# Main_old.net
KiCad netlist of a schematic drawn in EAGLE
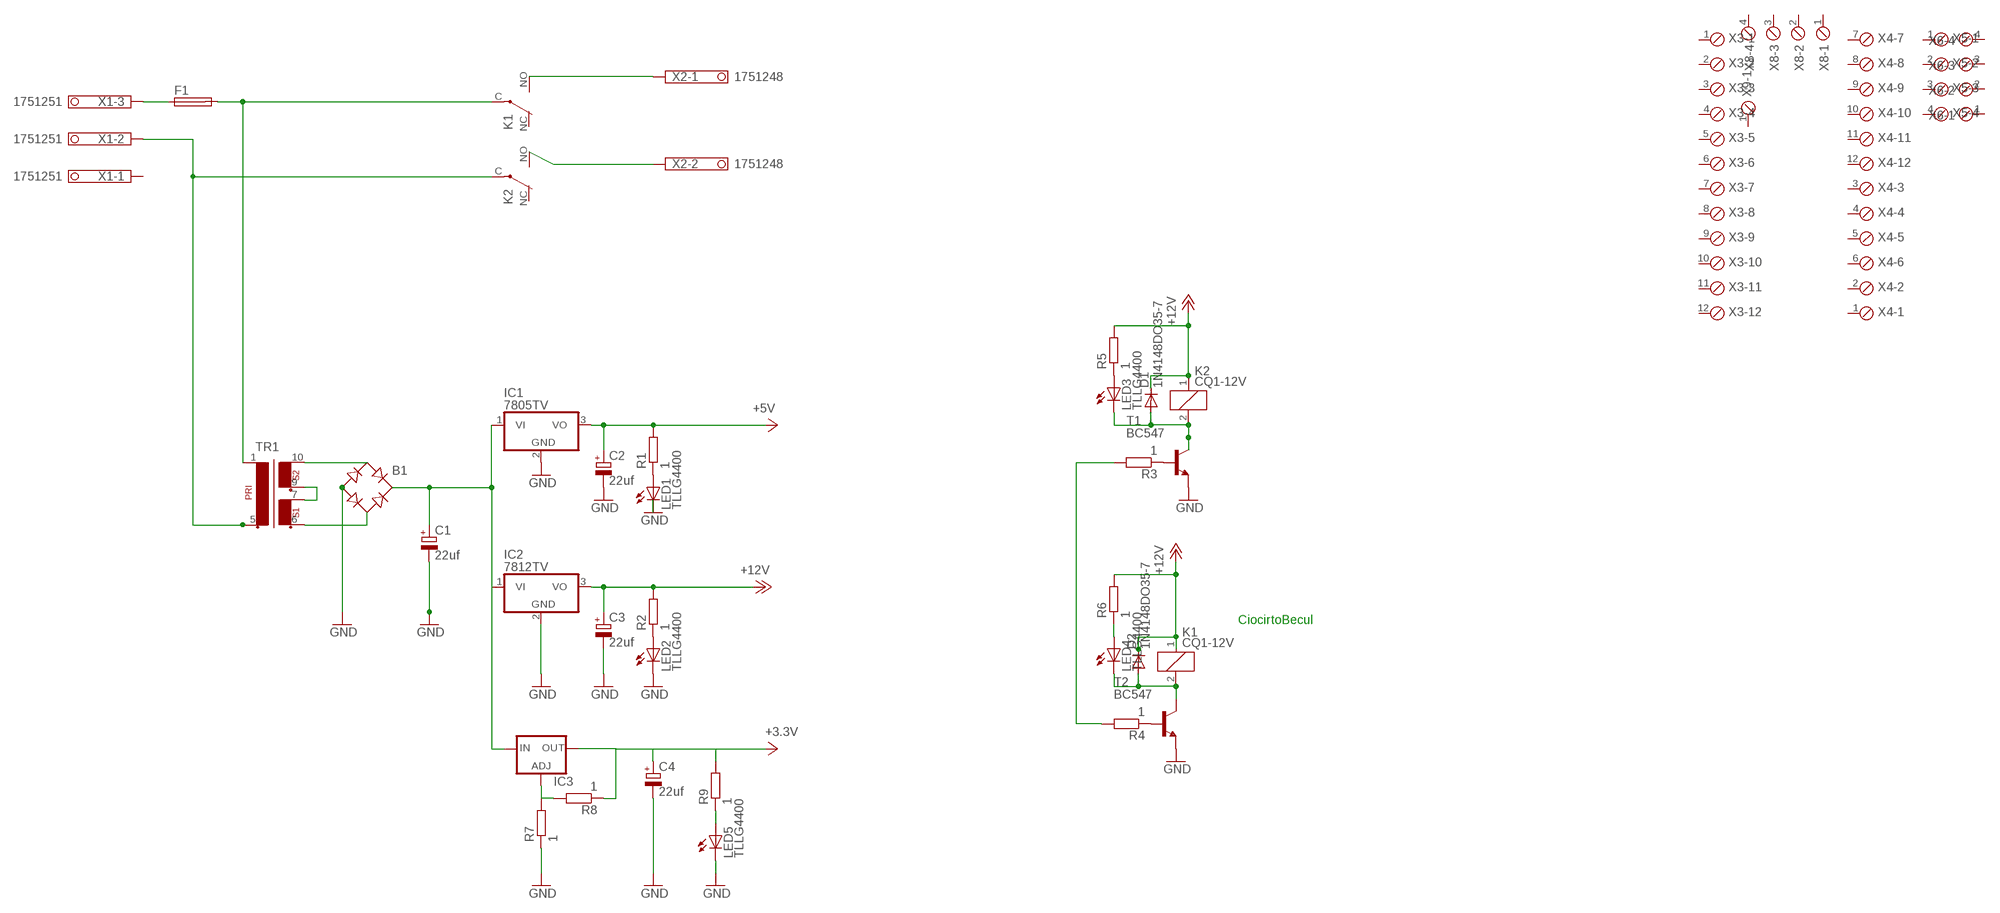
[diagram p0: schematic, sheet 1]

(export (version "E")
  (design (tool "Eeschema 10.0.6"))
  (components
    (comp (ref "B1")
      (value "RB1A")
      (footprint "eagle-import:RB1A")
      (libsource (lib "eagle-import") (part "RB1A"))
    )
    (comp (ref "C1")
      (value "22uf")
      (footprint "eagle-import:E2-4")
      (libsource (lib "eagle-import") (part "CPOL-EUE2-4"))
    )
    (comp (ref "C2")
      (value "22uf")
      (footprint "eagle-import:E2-4")
      (libsource (lib "eagle-import") (part "CPOL-EUE2-4"))
    )
    (comp (ref "C3")
      (value "22uf")
      (footprint "eagle-import:E2-4")
      (libsource (lib "eagle-import") (part "CPOL-EUE2-4"))
    )
    (comp (ref "C4")
      (value "22uf")
      (footprint "eagle-import:E2-4")
      (libsource (lib "eagle-import") (part "CPOL-EUE2-4"))
    )
    (comp (ref "D1")
      (value "1N4148DO35-7")
      (footprint "eagle-import:DO35-7")
      (libsource (lib "eagle-import") (part "1N4148DO35-7"))
    )
    (comp (ref "D2")
      (value "1N4148DO35-7")
      (footprint "eagle-import:DO35-7")
      (libsource (lib "eagle-import") (part "1N4148DO35-7"))
    )
    (comp (ref "F1")
      (value "SH25")
      (footprint "eagle-import:SH25")
      (fields (field (name "MF") "SCHURTER") (field (name "MPN") "0031.8211"))
      (libsource (lib "eagle-import") (part "SH25"))
    )
    (comp (ref "IC1")
      (value "7805TV")
      (footprint "eagle-import:TO220V")
      (libsource (lib "eagle-import") (part "78TV05"))
    )
    (comp (ref "IC2")
      (value "7812TV")
      (footprint "eagle-import:TO220V")
      (libsource (lib "eagle-import") (part "78TV12"))
    )
    (comp (ref "IC3")
      (value "LM317TS")
      (footprint "eagle-import:317TS")
      (libsource (lib "eagle-import") (part "LM317TS"))
    )
    (comp (ref "K1")
      (value "CQ1-12V")
      (footprint "eagle-import:CQ1")
      (libsource (lib "eagle-import") (part "CQ1-12V"))
    )
    (comp (ref "K2")
      (value "CQ1-12V")
      (footprint "eagle-import:CQ1")
      (libsource (lib "eagle-import") (part "CQ1-12V"))
    )
    (comp (ref "LED1")
      (value "TLLG4400")
      (footprint "eagle-import:LED3MM")
      (fields (field (name "MF") "VISHAY SEMICONDUCTOR"))
      (libsource (lib "eagle-import") (part "TLLG4400"))
    )
    (comp (ref "LED2")
      (value "TLLG4400")
      (footprint "eagle-import:LED3MM")
      (fields (field (name "MF") "VISHAY SEMICONDUCTOR"))
      (libsource (lib "eagle-import") (part "TLLG4400"))
    )
    (comp (ref "LED3")
      (value "TLLG4400")
      (footprint "eagle-import:LED3MM")
      (fields (field (name "MF") "VISHAY SEMICONDUCTOR"))
      (libsource (lib "eagle-import") (part "TLLG4400"))
    )
    (comp (ref "LED4")
      (value "TLLG4400")
      (footprint "eagle-import:LED3MM")
      (fields (field (name "MF") "VISHAY SEMICONDUCTOR"))
      (libsource (lib "eagle-import") (part "TLLG4400"))
    )
    (comp (ref "LED5")
      (value "TLLG4400")
      (footprint "eagle-import:LED3MM")
      (fields (field (name "MF") "VISHAY SEMICONDUCTOR"))
      (libsource (lib "eagle-import") (part "TLLG4400"))
    )
    (comp (ref "R1")
      (value "1")
      (footprint "eagle-import:0204_5")
      (libsource (lib "eagle-import") (part "R-EU_0204/5"))
    )
    (comp (ref "R2")
      (value "1")
      (footprint "eagle-import:0204_5")
      (libsource (lib "eagle-import") (part "R-EU_0204/5"))
    )
    (comp (ref "R3")
      (value "1")
      (footprint "eagle-import:0204_5")
      (libsource (lib "eagle-import") (part "R-EU_0204/5"))
    )
    (comp (ref "R4")
      (value "1")
      (footprint "eagle-import:0204_5")
      (libsource (lib "eagle-import") (part "R-EU_0204/5"))
    )
    (comp (ref "R5")
      (value "1")
      (footprint "eagle-import:0204_5")
      (libsource (lib "eagle-import") (part "R-EU_0204/5"))
    )
    (comp (ref "R6")
      (value "1")
      (footprint "eagle-import:0204_5")
      (libsource (lib "eagle-import") (part "R-EU_0204/5"))
    )
    (comp (ref "R7")
      (value "1")
      (footprint "eagle-import:0204_5")
      (libsource (lib "eagle-import") (part "R-EU_0204/5"))
    )
    (comp (ref "R8")
      (value "1")
      (footprint "eagle-import:0204_5")
      (libsource (lib "eagle-import") (part "R-EU_0204/5"))
    )
    (comp (ref "R9")
      (value "1")
      (footprint "eagle-import:0204_5")
      (libsource (lib "eagle-import") (part "R-EU_0204/5"))
    )
    (comp (ref "T1")
      (value "BC547")
      (footprint "eagle-import:TO92")
      (libsource (lib "eagle-import") (part "BC547"))
    )
    (comp (ref "T2")
      (value "BC547")
      (footprint "eagle-import:TO92")
      (libsource (lib "eagle-import") (part "BC547"))
    )
    (comp (ref "TR1")
      (value "EI30-2")
      (footprint "eagle-import:EI30-2")
      (libsource (lib "eagle-import") (part "EI30-2"))
    )
    (comp (ref "X1")
      (value "1751251")
      (footprint "eagle-import:1751251")
      (libsource (lib "eagle-import") (part "1751251"))
    )
    (comp (ref "X2")
      (value "1751248")
      (footprint "eagle-import:1751248")
      (libsource (lib "eagle-import") (part "1751248"))
    )
    (comp (ref "X3")
      (value "MPT12")
      (footprint "eagle-import:12POL254")
      (libsource (lib "eagle-import") (part "MPT12"))
    )
    (comp (ref "X4")
      (value "MPT12")
      (footprint "eagle-import:12POL254")
      (libsource (lib "eagle-import") (part "MPT12"))
    )
    (comp (ref "X5")
      (value "MPT4")
      (footprint "eagle-import:4POL254")
      (libsource (lib "eagle-import") (part "MPT4"))
    )
    (comp (ref "X6")
      (value "MPT4")
      (footprint "eagle-import:4POL254")
      (libsource (lib "eagle-import") (part "MPT4"))
    )
    (comp (ref "X8")
      (value "MPT4")
      (footprint "eagle-import:4POL254")
      (libsource (lib "eagle-import") (part "MPT4"))
    )
    (comp (ref "X9")
      (value "MPT2")
      (footprint "eagle-import:2POL254")
      (libsource (lib "eagle-import") (part "MPT2"))
    )
  )
  (nets
    (net (code "1") (name "+3.3V") (class "Default")
      (node (ref "C4") (pin "+") (pinfunction "+_+") (pintype "passive"))
      (node (ref "IC3") (pin "2") (pinfunction "OUT_2") (pintype "passive"))
      (node (ref "R8") (pin "1") (pinfunction "1_1") (pintype "passive"))
      (node (ref "R9") (pin "2") (pinfunction "2_2") (pintype "passive"))
    )
    (net (code "2") (name "+5V") (class "Default")
      (node (ref "C2") (pin "+") (pinfunction "+_+") (pintype "passive"))
      (node (ref "IC1") (pin "3") (pinfunction "VO_3") (pintype "passive"))
      (node (ref "R1") (pin "2") (pinfunction "2_2") (pintype "passive"))
    )
    (net (code "3") (name "+12V") (class "Default")
      (node (ref "C3") (pin "+") (pinfunction "+_+") (pintype "passive"))
      (node (ref "D1") (pin "C") (pinfunction "C_C") (pintype "passive"))
      (node (ref "D2") (pin "C") (pinfunction "C_C") (pintype "passive"))
      (node (ref "IC2") (pin "3") (pinfunction "VO_3") (pintype "passive"))
      (node (ref "K1") (pin "1") (pinfunction "1_1") (pintype "passive"))
      (node (ref "K2") (pin "1") (pinfunction "1_1") (pintype "passive"))
      (node (ref "R2") (pin "2") (pinfunction "2_2") (pintype "passive"))
      (node (ref "R5") (pin "2") (pinfunction "2_2") (pintype "passive"))
      (node (ref "R6") (pin "2") (pinfunction "2_2") (pintype "passive"))
    )
    (net (code "4") (name "GND") (class "Default")
      (node (ref "B1") (pin "-") (pinfunction "-_-") (pintype "passive"))
      (node (ref "C1") (pin "-") (pinfunction "-_-") (pintype "passive"))
      (node (ref "C2") (pin "-") (pinfunction "-_-") (pintype "passive"))
      (node (ref "C3") (pin "-") (pinfunction "-_-") (pintype "passive"))
      (node (ref "C4") (pin "-") (pinfunction "-_-") (pintype "passive"))
      (node (ref "IC1") (pin "2") (pinfunction "GND_2") (pintype "passive"))
      (node (ref "IC2") (pin "2") (pinfunction "GND_2") (pintype "passive"))
      (node (ref "LED1") (pin "K") (pinfunction "C_K") (pintype "passive"))
      (node (ref "LED2") (pin "K") (pinfunction "C_K") (pintype "passive"))
      (node (ref "LED5") (pin "K") (pinfunction "C_K") (pintype "passive"))
      (node (ref "R7") (pin "1") (pinfunction "1_1") (pintype "passive"))
      (node (ref "T1") (pin "1") (pinfunction "E_1") (pintype "passive"))
      (node (ref "T2") (pin "1") (pinfunction "E_1") (pintype "passive"))
    )
    (net (code "5") (name "Net-(IC1-VI)") (class "Default")
      (node (ref "B1") (pin "+") (pinfunction "+_+") (pintype "passive"))
      (node (ref "C1") (pin "+") (pinfunction "+_+") (pintype "passive"))
      (node (ref "IC1") (pin "1") (pinfunction "VI_1") (pintype "input"))
      (node (ref "IC2") (pin "1") (pinfunction "VI_1") (pintype "input"))
      (node (ref "IC3") (pin "3") (pinfunction "IN_3") (pintype "input"))
    )
    (net (code "6") (name "Net-(IC3-ADJ)") (class "Default")
      (node (ref "IC3") (pin "1") (pinfunction "ADJ_1") (pintype "input"))
      (node (ref "R7") (pin "2") (pinfunction "2_2") (pintype "passive"))
      (node (ref "R8") (pin "2") (pinfunction "2_2") (pintype "passive"))
    )
    (net (code "7") (name "Net-(K1B-P)") (class "Default")
      (node (ref "F1") (pin "2") (pinfunction "2_2") (pintype "passive"))
      (node (ref "K1") (pin "C") (pinfunction "P_C") (pintype "passive"))
      (node (ref "TR1") (pin "1") (pinfunction "1_1") (pintype "passive"))
    )
    (net (code "8") (name "Net-(K1B-S)") (class "Default")
      (node (ref "K1") (pin "NO") (pinfunction "S_NO") (pintype "passive"))
      (node (ref "X2") (pin "1") (pinfunction "K_1") (pintype "passive"))
    )
    (net (code "9") (name "Net-(K2B-P)") (class "Default")
      (node (ref "K2") (pin "C") (pinfunction "P_C") (pintype "passive"))
      (node (ref "TR1") (pin "5") (pinfunction "2_5") (pintype "passive"))
      (node (ref "X1") (pin "2") (pinfunction "K_2") (pintype "passive"))
    )
    (net (code "10") (name "Net-(K2B-S)") (class "Default")
      (node (ref "K2") (pin "NO") (pinfunction "S_NO") (pintype "passive"))
      (node (ref "X2") (pin "2") (pinfunction "K_2") (pintype "passive"))
    )
    (net (code "11") (name "Net-(LED1-PadA)") (class "Default")
      (node (ref "LED1") (pin "A") (pinfunction "A_A") (pintype "passive"))
      (node (ref "R1") (pin "1") (pinfunction "1_1") (pintype "passive"))
    )
    (net (code "12") (name "Net-(LED2-PadA)") (class "Default")
      (node (ref "LED2") (pin "A") (pinfunction "A_A") (pintype "passive"))
      (node (ref "R2") (pin "1") (pinfunction "1_1") (pintype "passive"))
    )
    (net (code "13") (name "Net-(LED3-C)") (class "Default")
      (node (ref "D1") (pin "A") (pinfunction "A_A") (pintype "passive"))
      (node (ref "K2") (pin "2") (pinfunction "2_2") (pintype "passive"))
      (node (ref "LED3") (pin "K") (pinfunction "C_K") (pintype "passive"))
      (node (ref "T1") (pin "3") (pinfunction "C_3") (pintype "passive"))
    )
    (net (code "14") (name "Net-(LED3-PadA)") (class "Default")
      (node (ref "LED3") (pin "A") (pinfunction "A_A") (pintype "passive"))
      (node (ref "R5") (pin "1") (pinfunction "1_1") (pintype "passive"))
    )
    (net (code "15") (name "Net-(LED4-C)") (class "Default")
      (node (ref "D2") (pin "A") (pinfunction "A_A") (pintype "passive"))
      (node (ref "K1") (pin "2") (pinfunction "2_2") (pintype "passive"))
      (node (ref "LED4") (pin "K") (pinfunction "C_K") (pintype "passive"))
      (node (ref "T2") (pin "3") (pinfunction "C_3") (pintype "passive"))
    )
    (net (code "16") (name "Net-(LED4-PadA)") (class "Default")
      (node (ref "LED4") (pin "A") (pinfunction "A_A") (pintype "passive"))
      (node (ref "R6") (pin "1") (pinfunction "1_1") (pintype "passive"))
    )
    (net (code "17") (name "Net-(LED5-PadA)") (class "Default")
      (node (ref "LED5") (pin "A") (pinfunction "A_A") (pintype "passive"))
      (node (ref "R9") (pin "1") (pinfunction "1_1") (pintype "passive"))
    )
    (net (code "18") (name "Net-(R3-Pad2)") (class "Default")
      (node (ref "R3") (pin "2") (pinfunction "2_2") (pintype "passive"))
      (node (ref "R4") (pin "2") (pinfunction "2_2") (pintype "passive"))
    )
    (net (code "19") (name "Net-(T1-B)") (class "Default")
      (node (ref "R3") (pin "1") (pinfunction "1_1") (pintype "passive"))
      (node (ref "T1") (pin "2") (pinfunction "B_2") (pintype "passive"))
    )
    (net (code "20") (name "Net-(T2-B)") (class "Default")
      (node (ref "R4") (pin "1") (pinfunction "1_1") (pintype "passive"))
      (node (ref "T2") (pin "2") (pinfunction "B_2") (pintype "passive"))
    )
    (net (code "21") (name "Net-(TR1-3)") (class "Default")
      (node (ref "B1") (pin "AC2") (pinfunction "AC2_AC2") (pintype "passive"))
      (node (ref "TR1") (pin "6") (pinfunction "3_6") (pintype "passive"))
    )
    (net (code "22") (name "Net-(TR1-4)") (class "Default")
      (node (ref "TR1") (pin "7") (pinfunction "4_7") (pintype "passive"))
      (node (ref "TR1") (pin "9") (pinfunction "5_9") (pintype "passive"))
    )
    (net (code "23") (name "Net-(TR1-6)") (class "Default")
      (node (ref "B1") (pin "AC1") (pinfunction "AC1_AC1") (pintype "passive"))
      (node (ref "TR1") (pin "10") (pinfunction "6_10") (pintype "passive"))
    )
    (net (code "24") (name "Net-(X1C-K)") (class "Default")
      (node (ref "F1") (pin "1") (pinfunction "1_1") (pintype "passive"))
      (node (ref "X1") (pin "3") (pinfunction "K_3") (pintype "passive"))
    )
    (net (code "25") (name "unconnected-(K1B-O-PadNC)") (class "Default")
      (node (ref "K1") (pin "NC") (pinfunction "O_NC") (pintype "passive"))
    )
    (net (code "26") (name "unconnected-(K2B-O-PadNC)") (class "Default")
      (node (ref "K2") (pin "NC") (pinfunction "O_NC") (pintype "passive"))
    )
    (net (code "27") (name "unconnected-(X1A-K-Pad1)") (class "Default")
      (node (ref "X1") (pin "1") (pinfunction "K_1") (pintype "passive"))
    )
    (net (code "28") (name "unconnected-(X3-Pad1)") (class "Default")
      (node (ref "X3") (pin "1") (pinfunction "1_1") (pintype "passive"))
    )
    (net (code "29") (name "unconnected-(X3B-1-Pad10)") (class "Default")
      (node (ref "X3") (pin "10") (pinfunction "1_10") (pintype "passive"))
    )
    (net (code "30") (name "unconnected-(X3C-1-Pad11)") (class "Default")
      (node (ref "X3") (pin "11") (pinfunction "1_11") (pintype "passive"))
    )
    (net (code "31") (name "unconnected-(X3D-1-Pad12)") (class "Default")
      (node (ref "X3") (pin "12") (pinfunction "1_12") (pintype "passive"))
    )
    (net (code "32") (name "unconnected-(X3E-1-Pad2)") (class "Default")
      (node (ref "X3") (pin "2") (pinfunction "1_2") (pintype "passive"))
    )
    (net (code "33") (name "unconnected-(X3F-1-Pad3)") (class "Default")
      (node (ref "X3") (pin "3") (pinfunction "1_3") (pintype "passive"))
    )
    (net (code "34") (name "unconnected-(X3G-1-Pad4)") (class "Default")
      (node (ref "X3") (pin "4") (pinfunction "1_4") (pintype "passive"))
    )
    (net (code "35") (name "unconnected-(X3H-1-Pad5)") (class "Default")
      (node (ref "X3") (pin "5") (pinfunction "1_5") (pintype "passive"))
    )
    (net (code "36") (name "unconnected-(X3I-1-Pad6)") (class "Default")
      (node (ref "X3") (pin "6") (pinfunction "1_6") (pintype "passive"))
    )
    (net (code "37") (name "unconnected-(X3J-1-Pad7)") (class "Default")
      (node (ref "X3") (pin "7") (pinfunction "1_7") (pintype "passive"))
    )
    (net (code "38") (name "unconnected-(X3K-1-Pad8)") (class "Default")
      (node (ref "X3") (pin "8") (pinfunction "1_8") (pintype "passive"))
    )
    (net (code "39") (name "unconnected-(X3L-1-Pad9)") (class "Default")
      (node (ref "X3") (pin "9") (pinfunction "1_9") (pintype "passive"))
    )
    (net (code "40") (name "unconnected-(X4-Pad1)") (class "Default")
      (node (ref "X4") (pin "1") (pinfunction "1_1") (pintype "passive"))
    )
    (net (code "41") (name "unconnected-(X4B-1-Pad10)") (class "Default")
      (node (ref "X4") (pin "10") (pinfunction "1_10") (pintype "passive"))
    )
    (net (code "42") (name "unconnected-(X4C-1-Pad11)") (class "Default")
      (node (ref "X4") (pin "11") (pinfunction "1_11") (pintype "passive"))
    )
    (net (code "43") (name "unconnected-(X4D-1-Pad12)") (class "Default")
      (node (ref "X4") (pin "12") (pinfunction "1_12") (pintype "passive"))
    )
    (net (code "44") (name "unconnected-(X4E-1-Pad2)") (class "Default")
      (node (ref "X4") (pin "2") (pinfunction "1_2") (pintype "passive"))
    )
    (net (code "45") (name "unconnected-(X4F-1-Pad3)") (class "Default")
      (node (ref "X4") (pin "3") (pinfunction "1_3") (pintype "passive"))
    )
    (net (code "46") (name "unconnected-(X4G-1-Pad4)") (class "Default")
      (node (ref "X4") (pin "4") (pinfunction "1_4") (pintype "passive"))
    )
    (net (code "47") (name "unconnected-(X4H-1-Pad5)") (class "Default")
      (node (ref "X4") (pin "5") (pinfunction "1_5") (pintype "passive"))
    )
    (net (code "48") (name "unconnected-(X4I-1-Pad6)") (class "Default")
      (node (ref "X4") (pin "6") (pinfunction "1_6") (pintype "passive"))
    )
    (net (code "49") (name "unconnected-(X4J-1-Pad7)") (class "Default")
      (node (ref "X4") (pin "7") (pinfunction "1_7") (pintype "passive"))
    )
    (net (code "50") (name "unconnected-(X4K-1-Pad8)") (class "Default")
      (node (ref "X4") (pin "8") (pinfunction "1_8") (pintype "passive"))
    )
    (net (code "51") (name "unconnected-(X4L-1-Pad9)") (class "Default")
      (node (ref "X4") (pin "9") (pinfunction "1_9") (pintype "passive"))
    )
    (net (code "52") (name "unconnected-(X5-Pad1)") (class "Default")
      (node (ref "X5") (pin "1") (pinfunction "1_1") (pintype "passive"))
    )
    (net (code "53") (name "unconnected-(X5B-1-Pad2)") (class "Default")
      (node (ref "X5") (pin "2") (pinfunction "1_2") (pintype "passive"))
    )
    (net (code "54") (name "unconnected-(X5C-1-Pad3)") (class "Default")
      (node (ref "X5") (pin "3") (pinfunction "1_3") (pintype "passive"))
    )
    (net (code "55") (name "unconnected-(X5D-1-Pad4)") (class "Default")
      (node (ref "X5") (pin "4") (pinfunction "1_4") (pintype "passive"))
    )
    (net (code "56") (name "unconnected-(X6-Pad1)") (class "Default")
      (node (ref "X6") (pin "1") (pinfunction "1_1") (pintype "passive"))
    )
    (net (code "57") (name "unconnected-(X6B-1-Pad2)") (class "Default")
      (node (ref "X6") (pin "2") (pinfunction "1_2") (pintype "passive"))
    )
    (net (code "58") (name "unconnected-(X6C-1-Pad3)") (class "Default")
      (node (ref "X6") (pin "3") (pinfunction "1_3") (pintype "passive"))
    )
    (net (code "59") (name "unconnected-(X6D-1-Pad4)") (class "Default")
      (node (ref "X6") (pin "4") (pinfunction "1_4") (pintype "passive"))
    )
    (net (code "60") (name "unconnected-(X8-Pad1)") (class "Default")
      (node (ref "X8") (pin "1") (pinfunction "1_1") (pintype "passive"))
    )
    (net (code "61") (name "unconnected-(X8B-1-Pad2)") (class "Default")
      (node (ref "X8") (pin "2") (pinfunction "1_2") (pintype "passive"))
    )
    (net (code "62") (name "unconnected-(X8C-1-Pad3)") (class "Default")
      (node (ref "X8") (pin "3") (pinfunction "1_3") (pintype "passive"))
    )
    (net (code "63") (name "unconnected-(X8D-1-Pad4)") (class "Default")
      (node (ref "X8") (pin "4") (pinfunction "1_4") (pintype "passive"))
    )
    (net (code "64") (name "unconnected-(X9-Pad1)") (class "Default")
      (node (ref "X9") (pin "1") (pinfunction "1_1") (pintype "passive"))
    )
  )
)
